# freiBot.net
KiCad netlist of a schematic drawn in EAGLE
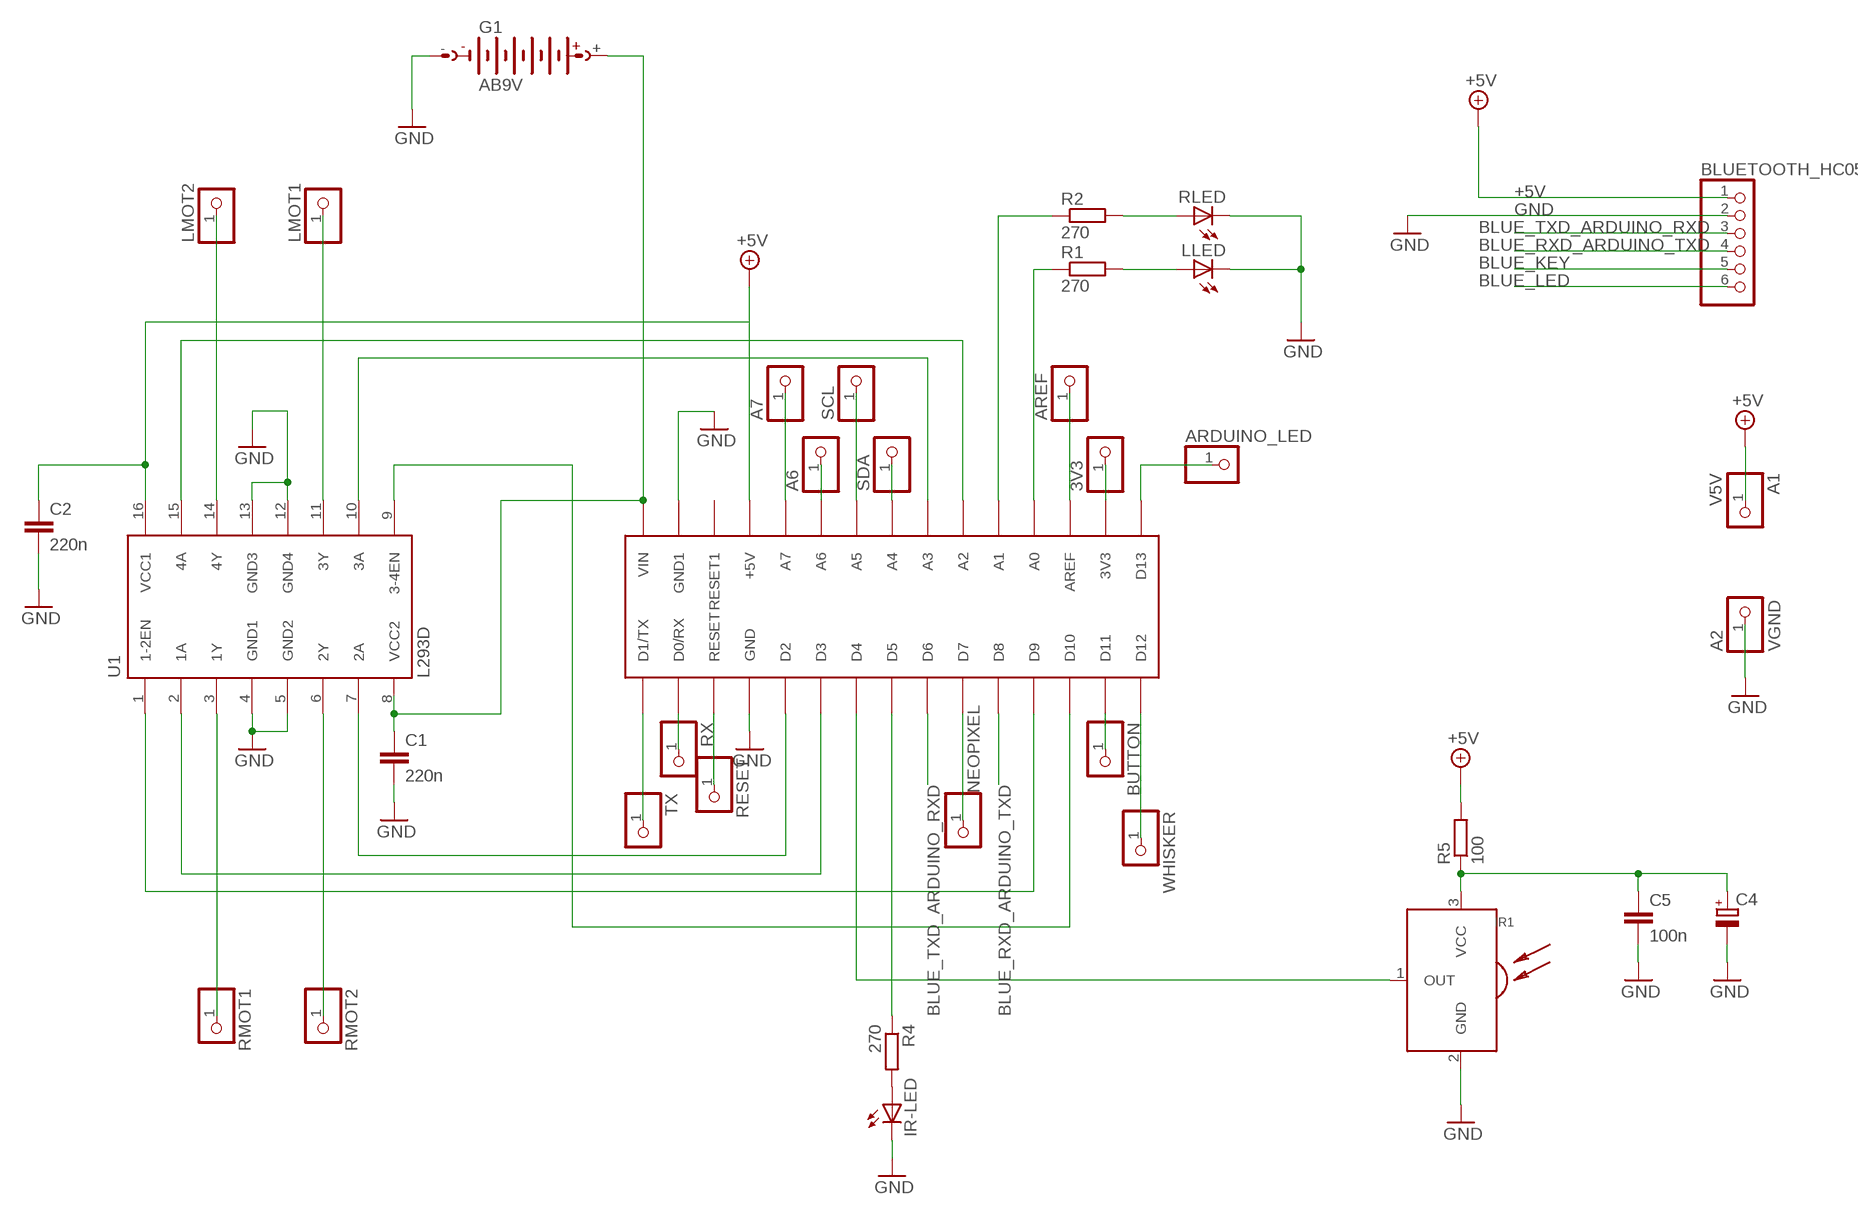
[diagram p0: schematic, sheet 1]

(export (version "E")
  (design (tool "Eeschema 10.0.6"))
  (components
    (comp (ref "3V3")
      (value "PINHD-1X1")
      (footprint "eagle-import:1X01")
      (libsource (lib "eagle-import") (part "PINHD-1X1"))
    )
    (comp (ref "A1")
      (value "V5V")
      (footprint "eagle-import:1X01")
      (libsource (lib "eagle-import") (part "PINHD-1X1"))
    )
    (comp (ref "A2")
      (value "VGND")
      (footprint "eagle-import:1X01")
      (libsource (lib "eagle-import") (part "PINHD-1X1"))
    )
    (comp (ref "A6")
      (value "PINHD-1X1")
      (footprint "eagle-import:1X01")
      (libsource (lib "eagle-import") (part "PINHD-1X1"))
    )
    (comp (ref "A7")
      (value "PINHD-1X1")
      (footprint "eagle-import:1X01")
      (libsource (lib "eagle-import") (part "PINHD-1X1"))
    )
    (comp (ref "ARDUINO_LED")
      (value "PINHD-1X1")
      (footprint "eagle-import:1X01")
      (libsource (lib "eagle-import") (part "PINHD-1X1"))
    )
    (comp (ref "AREF")
      (value "PINHD-1X1")
      (footprint "eagle-import:1X01")
      (libsource (lib "eagle-import") (part "PINHD-1X1"))
    )
    (comp (ref "BLUETOOTH_HC05")
      (value "PINHD-1X6")
      (footprint "eagle-import:1X06")
      (libsource (lib "eagle-import") (part "PINHD-1X6"))
    )
    (comp (ref "BUTTON")
      (value "PINHD-1X1")
      (footprint "eagle-import:1X01")
      (libsource (lib "eagle-import") (part "PINHD-1X1"))
    )
    (comp (ref "C1")
      (value "220n")
      (footprint "eagle-import:C075-042X103")
      (libsource (lib "eagle-import") (part "C-EU075-042X103"))
    )
    (comp (ref "C2")
      (value "220n")
      (footprint "eagle-import:C075-042X103")
      (libsource (lib "eagle-import") (part "C-EU075-042X103"))
    )
    (comp (ref "C4")
      (value "CPOL-EUE5-8.5")
      (footprint "eagle-import:E5-8,5")
      (libsource (lib "eagle-import") (part "CPOL-EUE5-8.5"))
    )
    (comp (ref "C5")
      (value "100n")
      (footprint "eagle-import:C050-025X075")
      (libsource (lib "eagle-import") (part "C-EU050-025X075"))
    )
    (comp (ref "G1")
      (value "AB9V")
      (footprint "eagle-import:AB9V")
      (libsource (lib "eagle-import") (part "AB9V"))
    )
    (comp (ref "IR-LED")
      (value "LED5MM")
      (footprint "eagle-import:LED5MM")
      (libsource (lib "eagle-import") (part "LED5MM"))
    )
    (comp (ref "IR1")
      (value "SFH5110")
      (footprint "eagle-import:SFH511_")
      (libsource (lib "eagle-import") (part "SFH5110"))
    )
    (comp (ref "LLED")
      (value "LED10MM")
      (footprint "eagle-import:LED10MM")
      (libsource (lib "eagle-import") (part "LED10MM"))
    )
    (comp (ref "LMOT1")
      (value "PINHD-1X1")
      (footprint "eagle-import:1X01")
      (libsource (lib "eagle-import") (part "PINHD-1X1"))
    )
    (comp (ref "LMOT2")
      (value "PINHD-1X1")
      (footprint "eagle-import:1X01")
      (libsource (lib "eagle-import") (part "PINHD-1X1"))
    )
    (comp (ref "NEOPIXEL")
      (value "PINHD-1X1")
      (footprint "eagle-import:1X01")
      (libsource (lib "eagle-import") (part "PINHD-1X1"))
    )
    (comp (ref "R1")
      (value "270")
      (footprint "eagle-import:0309_12")
      (libsource (lib "eagle-import") (part "R-EU_0309/12"))
    )
    (comp (ref "R2")
      (value "270")
      (footprint "eagle-import:0309_12")
      (libsource (lib "eagle-import") (part "R-EU_0309/12"))
    )
    (comp (ref "R4")
      (value "270")
      (footprint "eagle-import:0309_12")
      (libsource (lib "eagle-import") (part "R-EU_0309/12"))
    )
    (comp (ref "R5")
      (value "100")
      (footprint "eagle-import:0309_10")
      (libsource (lib "eagle-import") (part "R-EU_0309/10"))
    )
    (comp (ref "RESET")
      (value "PINHD-1X1")
      (footprint "eagle-import:1X01")
      (libsource (lib "eagle-import") (part "PINHD-1X1"))
    )
    (comp (ref "RLED")
      (value "LED10MM")
      (footprint "eagle-import:LED10MM")
      (libsource (lib "eagle-import") (part "LED10MM"))
    )
    (comp (ref "RMOT1")
      (value "PINHD-1X1")
      (footprint "eagle-import:1X01")
      (libsource (lib "eagle-import") (part "PINHD-1X1"))
    )
    (comp (ref "RMOT2")
      (value "PINHD-1X1")
      (footprint "eagle-import:1X01")
      (libsource (lib "eagle-import") (part "PINHD-1X1"))
    )
    (comp (ref "RX")
      (value "PINHD-1X1")
      (footprint "eagle-import:1X01")
      (libsource (lib "eagle-import") (part "PINHD-1X1"))
    )
    (comp (ref "SCL")
      (value "PINHD-1X1")
      (footprint "eagle-import:1X01")
      (libsource (lib "eagle-import") (part "PINHD-1X1"))
    )
    (comp (ref "SDA")
      (value "PINHD-1X1")
      (footprint "eagle-import:1X01")
      (libsource (lib "eagle-import") (part "PINHD-1X1"))
    )
    (comp (ref "TX")
      (value "PINHD-1X1")
      (footprint "eagle-import:1X01")
      (libsource (lib "eagle-import") (part "PINHD-1X1"))
    )
    (comp (ref "U1")
      (value "L293D")
      (footprint "eagle-import:DIL16")
      (libsource (lib "eagle-import") (part "L293D"))
    )
    (comp (ref "U2")
      (value "ARDUINONANO")
      (footprint "eagle-import:PDIP-32")
      (libsource (lib "eagle-import") (part "ARDUINONANO"))
    )
    (comp (ref "WHISKER")
      (value "PINHD-1X1")
      (footprint "eagle-import:1X01")
      (libsource (lib "eagle-import") (part "PINHD-1X1"))
    )
  )
  (nets
    (net (code "1") (name "+5V") (class "Default")
      (node (ref "A1") (pin "1") (pinfunction "1_1") (pintype "passive"))
      (node (ref "BLUETOOTH_HC05") (pin "1") (pinfunction "1_1") (pintype "passive"))
      (node (ref "C2") (pin "1") (pinfunction "1_1") (pintype "passive"))
      (node (ref "R5") (pin "2") (pinfunction "2_2") (pintype "passive"))
      (node (ref "U1") (pin "16") (pinfunction "VCC1_16") (pintype "power_in"))
      (node (ref "U2") (pin "+5V") (pinfunction "+5V_+5V") (pintype "bidirectional"))
    )
    (net (code "2") (name "/BLUE_KEY") (class "Default")
      (node (ref "BLUETOOTH_HC05") (pin "5") (pinfunction "5_5") (pintype "passive"))
    )
    (net (code "3") (name "/BLUE_LED") (class "Default")
      (node (ref "BLUETOOTH_HC05") (pin "6") (pinfunction "6_6") (pintype "passive"))
    )
    (net (code "4") (name "/BLUE_RXD_ARDUINO_TXD") (class "Default")
      (node (ref "BLUETOOTH_HC05") (pin "4") (pinfunction "4_4") (pintype "passive"))
      (node (ref "U2") (pin "D8") (pinfunction "D8_D8") (pintype "bidirectional"))
    )
    (net (code "5") (name "/BLUE_TXD_ARDUINO_RXD") (class "Default")
      (node (ref "BLUETOOTH_HC05") (pin "3") (pinfunction "3_3") (pintype "passive"))
      (node (ref "U2") (pin "D6") (pinfunction "D6_D6") (pintype "bidirectional"))
    )
    (net (code "6") (name "GND") (class "Default")
      (node (ref "A2") (pin "1") (pinfunction "1_1") (pintype "passive"))
      (node (ref "BLUETOOTH_HC05") (pin "2") (pinfunction "2_2") (pintype "passive"))
      (node (ref "C1") (pin "2") (pinfunction "2_2") (pintype "passive"))
      (node (ref "C2") (pin "2") (pinfunction "2_2") (pintype "passive"))
      (node (ref "C4") (pin "-") (pinfunction "-_-") (pintype "passive"))
      (node (ref "C5") (pin "2") (pinfunction "2_2") (pintype "passive"))
      (node (ref "G1") (pin "-") (pinfunction "-_-") (pintype "passive"))
      (node (ref "IR-LED") (pin "K") (pinfunction "C_K") (pintype "passive"))
      (node (ref "IR1") (pin "2") (pinfunction "GND_2") (pintype "power_in"))
      (node (ref "LLED") (pin "K") (pinfunction "C_K") (pintype "passive"))
      (node (ref "RLED") (pin "K") (pinfunction "C_K") (pintype "passive"))
      (node (ref "U1") (pin "12") (pinfunction "GND4_12") (pintype "power_in"))
      (node (ref "U1") (pin "13") (pinfunction "GND3_13") (pintype "power_in"))
      (node (ref "U1") (pin "4") (pinfunction "GND1_4") (pintype "power_in"))
      (node (ref "U1") (pin "5") (pinfunction "GND2_5") (pintype "power_in"))
      (node (ref "U2") (pin "GND") (pinfunction "GND_GND") (pintype "bidirectional"))
      (node (ref "U2") (pin "GND1") (pinfunction "GND1_GND1") (pintype "bidirectional"))
    )
    (net (code "7") (name "Net-(3V3-Pad1)") (class "Default")
      (node (ref "3V3") (pin "1") (pinfunction "1_1") (pintype "passive"))
      (node (ref "U2") (pin "3V3") (pinfunction "3V3_3V3") (pintype "bidirectional"))
    )
    (net (code "8") (name "Net-(A6-Pad1)") (class "Default")
      (node (ref "A6") (pin "1") (pinfunction "1_1") (pintype "passive"))
      (node (ref "U2") (pin "A6") (pinfunction "A6_A6") (pintype "bidirectional"))
    )
    (net (code "9") (name "Net-(A7-Pad1)") (class "Default")
      (node (ref "A7") (pin "1") (pinfunction "1_1") (pintype "passive"))
      (node (ref "U2") (pin "A7") (pinfunction "A7_A7") (pintype "bidirectional"))
    )
    (net (code "10") (name "Net-(ARDUINO_LED-Pad1)") (class "Default")
      (node (ref "ARDUINO_LED") (pin "1") (pinfunction "1_1") (pintype "passive"))
      (node (ref "U2") (pin "D13") (pinfunction "D13_D13") (pintype "bidirectional"))
    )
    (net (code "11") (name "Net-(AREF-Pad1)") (class "Default")
      (node (ref "AREF") (pin "1") (pinfunction "1_1") (pintype "passive"))
      (node (ref "U2") (pin "AREF") (pinfunction "AREF_AREF") (pintype "bidirectional"))
    )
    (net (code "12") (name "Net-(BUTTON-Pad1)") (class "Default")
      (node (ref "BUTTON") (pin "1") (pinfunction "1_1") (pintype "passive"))
      (node (ref "U2") (pin "D11") (pinfunction "D11_D11") (pintype "bidirectional"))
    )
    (net (code "13") (name "Net-(IR-LED-PadA)") (class "Default")
      (node (ref "IR-LED") (pin "A") (pinfunction "A_A") (pintype "passive"))
      (node (ref "R4") (pin "2") (pinfunction "2_2") (pintype "passive"))
    )
    (net (code "14") (name "Net-(IR1-OUT)") (class "Default")
      (node (ref "IR1") (pin "1") (pinfunction "OUT_1") (pintype "output"))
      (node (ref "U2") (pin "D4") (pinfunction "D4_D4") (pintype "bidirectional"))
    )
    (net (code "15") (name "Net-(IR1-VCC)") (class "Default")
      (node (ref "C4") (pin "+") (pinfunction "+_+") (pintype "passive"))
      (node (ref "C5") (pin "1") (pinfunction "1_1") (pintype "passive"))
      (node (ref "IR1") (pin "3") (pinfunction "VCC_3") (pintype "power_in"))
      (node (ref "R5") (pin "1") (pinfunction "1_1") (pintype "passive"))
    )
    (net (code "16") (name "Net-(LLED-PadA)") (class "Default")
      (node (ref "LLED") (pin "A") (pinfunction "A_A") (pintype "passive"))
      (node (ref "R1") (pin "2") (pinfunction "2_2") (pintype "passive"))
    )
    (net (code "17") (name "Net-(NEOPIXEL-Pad1)") (class "Default")
      (node (ref "NEOPIXEL") (pin "1") (pinfunction "1_1") (pintype "passive"))
      (node (ref "U2") (pin "D7") (pinfunction "D7_D7") (pintype "bidirectional"))
    )
    (net (code "18") (name "Net-(R1-Pad1)") (class "Default")
      (node (ref "R1") (pin "1") (pinfunction "1_1") (pintype "passive"))
      (node (ref "U2") (pin "A0") (pinfunction "A0_A0") (pintype "bidirectional"))
    )
    (net (code "19") (name "Net-(R2-Pad1)") (class "Default")
      (node (ref "R2") (pin "1") (pinfunction "1_1") (pintype "passive"))
      (node (ref "U2") (pin "A1") (pinfunction "A1_A1") (pintype "bidirectional"))
    )
    (net (code "20") (name "Net-(R2-Pad2)") (class "Default")
      (node (ref "R2") (pin "2") (pinfunction "2_2") (pintype "passive"))
      (node (ref "RLED") (pin "A") (pinfunction "A_A") (pintype "passive"))
    )
    (net (code "21") (name "Net-(R4-Pad1)") (class "Default")
      (node (ref "R4") (pin "1") (pinfunction "1_1") (pintype "passive"))
      (node (ref "U2") (pin "D5") (pinfunction "D5_D5") (pintype "bidirectional"))
    )
    (net (code "22") (name "Net-(RESET-Pad1)") (class "Default")
      (node (ref "RESET") (pin "1") (pinfunction "1_1") (pintype "passive"))
      (node (ref "U2") (pin "RESET") (pinfunction "RESET_RESET") (pintype "bidirectional"))
    )
    (net (code "23") (name "Net-(RX-Pad1)") (class "Default")
      (node (ref "RX") (pin "1") (pinfunction "1_1") (pintype "passive"))
      (node (ref "U2") (pin "D0/RX") (pinfunction "D0/RX_D0/RX") (pintype "bidirectional"))
    )
    (net (code "24") (name "Net-(SCL-Pad1)") (class "Default")
      (node (ref "SCL") (pin "1") (pinfunction "1_1") (pintype "passive"))
      (node (ref "U2") (pin "A5") (pinfunction "A5_A5") (pintype "bidirectional"))
    )
    (net (code "25") (name "Net-(SDA-Pad1)") (class "Default")
      (node (ref "SDA") (pin "1") (pinfunction "1_1") (pintype "passive"))
      (node (ref "U2") (pin "A4") (pinfunction "A4_A4") (pintype "bidirectional"))
    )
    (net (code "26") (name "Net-(TX-Pad1)") (class "Default")
      (node (ref "TX") (pin "1") (pinfunction "1_1") (pintype "passive"))
      (node (ref "U2") (pin "D1/TX") (pinfunction "D1/TX_D1/TX") (pintype "bidirectional"))
    )
    (net (code "27") (name "Net-(U1-1-2EN)") (class "Default")
      (node (ref "U1") (pin "1") (pinfunction "1-2EN_1") (pintype "input"))
      (node (ref "U2") (pin "D9") (pinfunction "D9_D9") (pintype "bidirectional"))
    )
    (net (code "28") (name "Net-(U1-1A)") (class "Default")
      (node (ref "U1") (pin "2") (pinfunction "1A_2") (pintype "input"))
      (node (ref "U2") (pin "D3") (pinfunction "D3_D3") (pintype "bidirectional"))
    )
    (net (code "29") (name "Net-(U1-1Y)") (class "Default")
      (node (ref "RMOT1") (pin "1") (pinfunction "1_1") (pintype "passive"))
      (node (ref "U1") (pin "3") (pinfunction "1Y_3") (pintype "output"))
    )
    (net (code "30") (name "Net-(U1-2A)") (class "Default")
      (node (ref "U1") (pin "7") (pinfunction "2A_7") (pintype "input"))
      (node (ref "U2") (pin "D2") (pinfunction "D2_D2") (pintype "bidirectional"))
    )
    (net (code "31") (name "Net-(U1-2Y)") (class "Default")
      (node (ref "RMOT2") (pin "1") (pinfunction "1_1") (pintype "passive"))
      (node (ref "U1") (pin "6") (pinfunction "2Y_6") (pintype "output"))
    )
    (net (code "32") (name "Net-(U1-3-4EN)") (class "Default")
      (node (ref "U1") (pin "9") (pinfunction "3-4EN_9") (pintype "input"))
      (node (ref "U2") (pin "D10") (pinfunction "D10_D10") (pintype "bidirectional"))
    )
    (net (code "33") (name "Net-(U1-3A)") (class "Default")
      (node (ref "U1") (pin "10") (pinfunction "3A_10") (pintype "input"))
      (node (ref "U2") (pin "A3") (pinfunction "A3_A3") (pintype "bidirectional"))
    )
    (net (code "34") (name "Net-(U1-3Y)") (class "Default")
      (node (ref "LMOT1") (pin "1") (pinfunction "1_1") (pintype "passive"))
      (node (ref "U1") (pin "11") (pinfunction "3Y_11") (pintype "output"))
    )
    (net (code "35") (name "Net-(U1-4A)") (class "Default")
      (node (ref "U1") (pin "15") (pinfunction "4A_15") (pintype "input"))
      (node (ref "U2") (pin "A2") (pinfunction "A2_A2") (pintype "bidirectional"))
    )
    (net (code "36") (name "Net-(U1-4Y)") (class "Default")
      (node (ref "LMOT2") (pin "1") (pinfunction "1_1") (pintype "passive"))
      (node (ref "U1") (pin "14") (pinfunction "4Y_14") (pintype "output"))
    )
    (net (code "37") (name "Net-(U1-VCC2)") (class "Default")
      (node (ref "C1") (pin "1") (pinfunction "1_1") (pintype "passive"))
      (node (ref "G1") (pin "+") (pinfunction "+_+") (pintype "passive"))
      (node (ref "U1") (pin "8") (pinfunction "VCC2_8") (pintype "power_in"))
      (node (ref "U2") (pin "VIN") (pinfunction "VIN_VIN") (pintype "bidirectional"))
    )
    (net (code "38") (name "Net-(U2-PadD12)") (class "Default")
      (node (ref "U2") (pin "D12") (pinfunction "D12_D12") (pintype "bidirectional"))
      (node (ref "WHISKER") (pin "1") (pinfunction "1_1") (pintype "passive"))
    )
    (net (code "39") (name "unconnected-(U2-PadRESET1)") (class "Default")
      (node (ref "U2") (pin "RESET1") (pinfunction "RESET1_RESET1") (pintype "bidirectional"))
    )
  )
)
